# STM32.net
KiCad netlist of a schematic drawn in Altium Designer
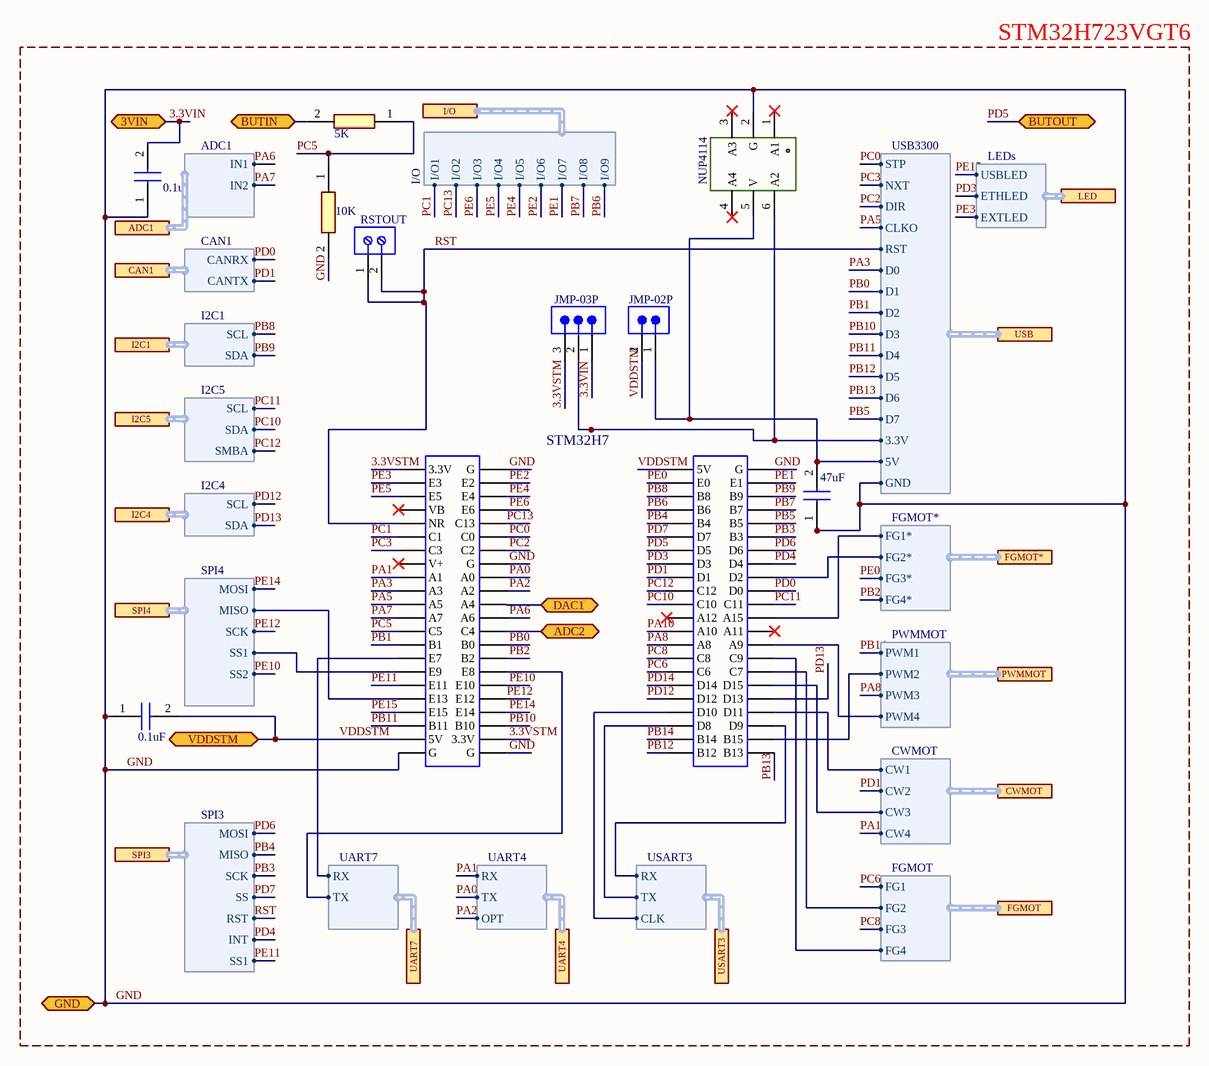
[diagram p0: STM32.SchDoc]

(export (version "E")
  (design (tool "Eeschema 10.0.6"))
  (components
    (comp (ref "BUTIN1")
      (value "5K")
      (footprint "RES0805")
      (description "RES-SMD0805")
      (libsource (lib "Components_Robots") (part "RES0805"))
    )
    (comp (ref "BUTIN2")
      (value "10K")
      (footprint "RES0805")
      (description "RES-SMD0805")
      (libsource (lib "") (part "RES0805_1"))
    )
    (comp (ref "CAP5VUSB")
      (value "47uF")
      (footprint "К10-17Б")
      (description "К10-17Б")
      (libsource (lib "Components_Robots") (part "CAP"))
    )
    (comp (ref "CAPSTM3V")
      (value "0.1uF")
      (footprint "CAP0805")
      (description "CAP-SMD0805")
      (libsource (lib "Components_Robots") (part "CAP0805"))
    )
    (comp (ref "CAPSTM5V")
      (value "0.1uF")
      (footprint "CAP0805")
      (description "CAP-SMD0805")
      (libsource (lib "Components_Robots") (part "CAP0805"))
    )
    (comp (ref "ESDUSB")
      (value "NUP4114")
      (footprint "NUP4114")
      (description "NUP4114HMR6T1G")
      (libsource (lib "Components_Robots") (part "NUP4114"))
    )
    (comp (ref "JMP3VUSB")
      (value "JMP-03P")
      (footprint "JMP-03P")
      (description "PLS-1x3")
      (libsource (lib "Components_Robots") (part "JMP-03P"))
    )
    (comp (ref "JMP5VUSB")
      (value "JMP-02P")
      (footprint "JMP-02P")
      (description "PLS-1x2")
      (libsource (lib "Components_Robots") (part "JMP-02P"))
    )
    (comp (ref "RSTOUT")
      (value "DG127-5.0-02P")
      (footprint "DG127-5.0-02P")
      (description "DG127-5.0-02P-14-00Z")
      (libsource (lib "Components_Robots") (part "DG127-5.0-02P"))
    )
    (comp (ref "STM")
      (value "STM32H7")
      (footprint "STM32H7")
      (description "STM32H723VGT6")
      (libsource (lib "Components_Robots") (part "STM32H7"))
    )
  )
  (nets
    (net (code "18") (name "/3.3V") (class "Default")
      (node (ref "ESDUSB") (pin "6") (pinfunction "A2_6") (pintype "passive"))
      (node (ref "JMP3VUSB") (pin "2") (pinfunction "2_2") (pintype "passive"))
    )
    (net (code "19") (name "/3.3VIN") (class "Default")
      (node (ref "CAPSTM3V") (pin "2") (pinfunction "2_2") (pintype "passive"))
      (node (ref "JMP3VUSB") (pin "1") (pinfunction "1_1") (pintype "passive"))
    )
    (net (code "20") (name "/3.3VSTM") (class "Default")
      (node (ref "JMP3VUSB") (pin "3") (pinfunction "3_3") (pintype "passive"))
      (node (ref "STM") (pin "3.3V") (pinfunction "3.3V_3.3V") (pintype "passive"))
    )
    (net (code "21") (name "/5V") (class "Default")
      (node (ref "CAP5VUSB") (pin "2") (pinfunction "2_2") (pintype "passive"))
      (node (ref "ESDUSB") (pin "5") (pinfunction "V_5") (pintype "passive"))
      (node (ref "JMP5VUSB") (pin "1") (pinfunction "1_1") (pintype "passive"))
    )
    (net (code "22") (name "/ADC2") (class "Default")
      (node (ref "STM") (pin "C4") (pinfunction "C4_C4") (pintype "passive"))
    )
    (net (code "23") (name "/BUTIN") (class "Default")
      (node (ref "BUTIN1") (pin "2") (pinfunction "2_2") (pintype "passive"))
    )
    (net (code "24") (name "/CLK") (class "Default")
      (node (ref "STM") (pin "D10") (pinfunction "D10_D10") (pintype "passive"))
    )
    (net (code "25") (name "/CW1") (class "Default")
      (node (ref "STM") (pin "D11") (pinfunction "D11_D11") (pintype "passive"))
    )
    (net (code "26") (name "/CW3") (class "Default")
      (node (ref "STM") (pin "D15") (pinfunction "D15_D15") (pintype "passive"))
    )
    (net (code "27") (name "/DAC1") (class "Default")
      (node (ref "STM") (pin "A4") (pinfunction "A4_A4") (pintype "passive"))
    )
    (net (code "28") (name "/FG1*") (class "Default")
      (node (ref "STM") (pin "A15") (pinfunction "A15_A15") (pintype "passive"))
    )
    (net (code "29") (name "/FG2") (class "Default")
      (node (ref "STM") (pin "C7") (pinfunction "C7_C7") (pintype "passive"))
    )
    (net (code "30") (name "/FG2*") (class "Default")
      (node (ref "STM") (pin "D2") (pinfunction "D2_D2") (pintype "passive"))
    )
    (net (code "31") (name "/FG4") (class "Default")
      (node (ref "STM") (pin "C9") (pinfunction "C9_C9") (pintype "passive"))
    )
    (net (code "32") (name "/GND") (class "Default")
      (node (ref "BUTIN2") (pin "2") (pinfunction "2_2") (pintype "passive"))
      (node (ref "CAP5VUSB") (pin "1") (pinfunction "1_1") (pintype "passive"))
      (node (ref "CAPSTM3V") (pin "1") (pinfunction "1_1") (pintype "passive"))
      (node (ref "CAPSTM5V") (pin "1") (pinfunction "1_1") (pintype "passive"))
      (node (ref "ESDUSB") (pin "2") (pinfunction "G_2") (pintype "passive"))
      (node (ref "STM") (pin "G") (pinfunction "G_G") (pintype "passive"))
    )
    (net (code "33") (name "/PA0") (class "Default")
      (node (ref "STM") (pin "A0") (pinfunction "A0_A0") (pintype "passive"))
    )
    (net (code "34") (name "/PA1") (class "Default")
      (node (ref "STM") (pin "A1") (pinfunction "A1_A1") (pintype "passive"))
    )
    (net (code "35") (name "/PA2") (class "Default")
      (node (ref "STM") (pin "A2") (pinfunction "A2_A2") (pintype "passive"))
    )
    (net (code "36") (name "/PA3") (class "Default")
      (node (ref "STM") (pin "A3") (pinfunction "A3_A3") (pintype "passive"))
    )
    (net (code "37") (name "/PA5") (class "Default")
      (node (ref "STM") (pin "A5") (pinfunction "A5_A5") (pintype "passive"))
    )
    (net (code "38") (name "/PA6") (class "Default")
      (node (ref "STM") (pin "A6") (pinfunction "A6_A6") (pintype "passive"))
    )
    (net (code "39") (name "/PA7") (class "Default")
      (node (ref "STM") (pin "A7") (pinfunction "A7_A7") (pintype "passive"))
    )
    (net (code "40") (name "/PA8") (class "Default")
      (node (ref "STM") (pin "A8") (pinfunction "A8_A8") (pintype "passive"))
    )
    (net (code "41") (name "/PA10") (class "Default")
      (node (ref "STM") (pin "A10") (pinfunction "A10_A10") (pintype "passive"))
    )
    (net (code "42") (name "/PB0") (class "Default")
      (node (ref "STM") (pin "B0") (pinfunction "B0_B0") (pintype "passive"))
    )
    (net (code "43") (name "/PB1") (class "Default")
      (node (ref "STM") (pin "B1") (pinfunction "B1_B1") (pintype "passive"))
    )
    (net (code "44") (name "/PB2") (class "Default")
      (node (ref "STM") (pin "B2") (pinfunction "B2_B2") (pintype "passive"))
    )
    (net (code "45") (name "/PB3") (class "Default")
      (node (ref "STM") (pin "B3") (pinfunction "B3_B3") (pintype "passive"))
    )
    (net (code "46") (name "/PB4") (class "Default")
      (node (ref "STM") (pin "B4") (pinfunction "B4_B4") (pintype "passive"))
    )
    (net (code "47") (name "/PB5") (class "Default")
      (node (ref "STM") (pin "B5") (pinfunction "B5_B5") (pintype "passive"))
    )
    (net (code "48") (name "/PB6") (class "Default")
      (node (ref "STM") (pin "B6") (pinfunction "B6_B6") (pintype "passive"))
    )
    (net (code "49") (name "/PB7") (class "Default")
      (node (ref "STM") (pin "B7") (pinfunction "B7_B7") (pintype "passive"))
    )
    (net (code "50") (name "/PB8") (class "Default")
      (node (ref "STM") (pin "B8") (pinfunction "B8_B8") (pintype "passive"))
    )
    (net (code "51") (name "/PB9") (class "Default")
      (node (ref "STM") (pin "B9") (pinfunction "B9_B9") (pintype "passive"))
    )
    (net (code "52") (name "/PB10") (class "Default")
      (node (ref "STM") (pin "B10") (pinfunction "B10_B10") (pintype "passive"))
    )
    (net (code "53") (name "/PB11") (class "Default")
      (node (ref "STM") (pin "B11") (pinfunction "B11_B11") (pintype "passive"))
    )
    (net (code "54") (name "/PB12") (class "Default")
      (node (ref "STM") (pin "B12") (pinfunction "B12_B12") (pintype "passive"))
    )
    (net (code "55") (name "/PB13") (class "Default")
      (node (ref "STM") (pin "B13") (pinfunction "B13_B13") (pintype "passive"))
    )
    (net (code "56") (name "/PB14") (class "Default")
      (node (ref "STM") (pin "B14") (pinfunction "B14_B14") (pintype "passive"))
    )
    (net (code "57") (name "/PC0") (class "Default")
      (node (ref "STM") (pin "C0") (pinfunction "C0_C0") (pintype "passive"))
    )
    (net (code "58") (name "/PC1") (class "Default")
      (node (ref "STM") (pin "C1") (pinfunction "C1_C1") (pintype "passive"))
    )
    (net (code "59") (name "/PC2") (class "Default")
      (node (ref "STM") (pin "C2") (pinfunction "C2_C2") (pintype "passive"))
    )
    (net (code "60") (name "/PC3") (class "Default")
      (node (ref "STM") (pin "C3") (pinfunction "C3_C3") (pintype "passive"))
    )
    (net (code "61") (name "/PC5") (class "Default")
      (node (ref "BUTIN1") (pin "1") (pinfunction "1_1") (pintype "passive"))
      (node (ref "BUTIN2") (pin "1") (pinfunction "1_1") (pintype "passive"))
      (node (ref "STM") (pin "C5") (pinfunction "C5_C5") (pintype "passive"))
    )
    (net (code "62") (name "/PC6") (class "Default")
      (node (ref "STM") (pin "C6") (pinfunction "C6_C6") (pintype "passive"))
    )
    (net (code "63") (name "/PC8") (class "Default")
      (node (ref "STM") (pin "C8") (pinfunction "C8_C8") (pintype "passive"))
    )
    (net (code "64") (name "/PC10") (class "Default")
      (node (ref "STM") (pin "C10") (pinfunction "C10_C10") (pintype "passive"))
    )
    (net (code "65") (name "/PC11") (class "Default")
      (node (ref "STM") (pin "C11") (pinfunction "C11_C11") (pintype "passive"))
    )
    (net (code "66") (name "/PC12") (class "Default")
      (node (ref "STM") (pin "C12") (pinfunction "C12_C12") (pintype "passive"))
    )
    (net (code "67") (name "/PC13") (class "Default")
      (node (ref "STM") (pin "C13") (pinfunction "C13_C13") (pintype "passive"))
    )
    (net (code "68") (name "/PD0") (class "Default")
      (node (ref "STM") (pin "D0") (pinfunction "D0_D0") (pintype "passive"))
    )
    (net (code "69") (name "/PD1") (class "Default")
      (node (ref "STM") (pin "D1") (pinfunction "D1_D1") (pintype "passive"))
    )
    (net (code "70") (name "/PD3") (class "Default")
      (node (ref "STM") (pin "D3") (pinfunction "D3_D3") (pintype "passive"))
    )
    (net (code "71") (name "/PD4") (class "Default")
      (node (ref "STM") (pin "D4") (pinfunction "D4_D4") (pintype "passive"))
    )
    (net (code "72") (name "/PD5") (class "Default")
      (node (ref "STM") (pin "D5") (pinfunction "D5_D5") (pintype "passive"))
    )
    (net (code "73") (name "/PD6") (class "Default")
      (node (ref "STM") (pin "D6") (pinfunction "D6_D6") (pintype "passive"))
    )
    (net (code "74") (name "/PD7") (class "Default")
      (node (ref "STM") (pin "D7") (pinfunction "D7_D7") (pintype "passive"))
    )
    (net (code "75") (name "/PD12") (class "Default")
      (node (ref "STM") (pin "D12") (pinfunction "D12_D12") (pintype "passive"))
    )
    (net (code "76") (name "/PD13") (class "Default")
      (node (ref "STM") (pin "D13") (pinfunction "D13_D13") (pintype "passive"))
    )
    (net (code "77") (name "/PD14") (class "Default")
      (node (ref "STM") (pin "D14") (pinfunction "D14_D14") (pintype "passive"))
    )
    (net (code "78") (name "/PE0") (class "Default")
      (node (ref "STM") (pin "E0") (pinfunction "E0_E0") (pintype "passive"))
    )
    (net (code "79") (name "/PE1") (class "Default")
      (node (ref "STM") (pin "E1") (pinfunction "E1_E1") (pintype "passive"))
    )
    (net (code "80") (name "/PE2") (class "Default")
      (node (ref "STM") (pin "E2") (pinfunction "E2_E2") (pintype "passive"))
    )
    (net (code "81") (name "/PE3") (class "Default")
      (node (ref "STM") (pin "E3") (pinfunction "E3_E3") (pintype "passive"))
    )
    (net (code "82") (name "/PE4") (class "Default")
      (node (ref "STM") (pin "E4") (pinfunction "E4_E4") (pintype "passive"))
    )
    (net (code "83") (name "/PE5") (class "Default")
      (node (ref "STM") (pin "E5") (pinfunction "E5_E5") (pintype "passive"))
    )
    (net (code "84") (name "/PE6") (class "Default")
      (node (ref "STM") (pin "E6") (pinfunction "E6_E6") (pintype "passive"))
    )
    (net (code "85") (name "/PE10") (class "Default")
      (node (ref "STM") (pin "E10") (pinfunction "E10_E10") (pintype "passive"))
    )
    (net (code "86") (name "/PE11") (class "Default")
      (node (ref "STM") (pin "E11") (pinfunction "E11_E11") (pintype "passive"))
    )
    (net (code "87") (name "/PE12") (class "Default")
      (node (ref "STM") (pin "E12") (pinfunction "E12_E12") (pintype "passive"))
    )
    (net (code "88") (name "/PE14") (class "Default")
      (node (ref "STM") (pin "E14") (pinfunction "E14_E14") (pintype "passive"))
    )
    (net (code "89") (name "/PE15") (class "Default")
      (node (ref "STM") (pin "E15") (pinfunction "E15_E15") (pintype "passive"))
    )
    (net (code "90") (name "/PWM2") (class "Default")
      (node (ref "STM") (pin "B15") (pinfunction "B15_B15") (pintype "passive"))
    )
    (net (code "91") (name "/PWM4") (class "Default")
      (node (ref "STM") (pin "A9") (pinfunction "A9_A9") (pintype "passive"))
    )
    (net (code "92") (name "/RST") (class "Default")
      (node (ref "RSTOUT") (pin "1") (pinfunction "1_1") (pintype "passive"))
      (node (ref "RSTOUT") (pin "2") (pinfunction "2_2") (pintype "passive"))
      (node (ref "STM") (pin "NR") (pinfunction "NR_NR") (pintype "passive"))
    )
    (net (code "93") (name "/VDDSTM") (class "Default")
      (node (ref "CAPSTM5V") (pin "2") (pinfunction "2_2") (pintype "passive"))
      (node (ref "JMP5VUSB") (pin "2") (pinfunction "2_2") (pintype "passive"))
      (node (ref "STM") (pin "5V") (pinfunction "5V_5V") (pintype "passive"))
    )
    (net (code "111") (name "unconnected-(ESDUSB-A1-Pad1)") (class "Default")
      (node (ref "ESDUSB") (pin "1") (pinfunction "A1_1") (pintype "passive+no_connect"))
    )
    (net (code "112") (name "unconnected-(ESDUSB-A3-Pad3)") (class "Default")
      (node (ref "ESDUSB") (pin "3") (pinfunction "A3_3") (pintype "passive+no_connect"))
    )
    (net (code "113") (name "unconnected-(ESDUSB-A4-Pad4)") (class "Default")
      (node (ref "ESDUSB") (pin "4") (pinfunction "A4_4") (pintype "passive+no_connect"))
    )
    (net (code "114") (name "unconnected-(STM-PadA11)") (class "Default")
      (node (ref "STM") (pin "A11") (pinfunction "A11_A11") (pintype "passive+no_connect"))
    )
    (net (code "115") (name "unconnected-(STM-PadA12)") (class "Default")
      (node (ref "STM") (pin "A12") (pinfunction "A12_A12") (pintype "passive+no_connect"))
    )
    (net (code "116") (name "unconnected-(STM-PadD8)") (class "Default")
      (node (ref "STM") (pin "D8") (pinfunction "D8_D8") (pintype "passive"))
    )
    (net (code "117") (name "unconnected-(STM-PadD9)") (class "Default")
      (node (ref "STM") (pin "D9") (pinfunction "D9_D9") (pintype "passive"))
    )
    (net (code "118") (name "unconnected-(STM-PadE7)") (class "Default")
      (node (ref "STM") (pin "E7") (pinfunction "E7_E7") (pintype "passive"))
    )
    (net (code "119") (name "unconnected-(STM-PadE8)") (class "Default")
      (node (ref "STM") (pin "E8") (pinfunction "E8_E8") (pintype "passive"))
    )
    (net (code "120") (name "unconnected-(STM-PadE9)") (class "Default")
      (node (ref "STM") (pin "E9") (pinfunction "E9_E9") (pintype "passive"))
    )
    (net (code "121") (name "unconnected-(STM-PadE13)") (class "Default")
      (node (ref "STM") (pin "E13") (pinfunction "E13_E13") (pintype "passive"))
    )
    (net (code "122") (name "unconnected-(STM-PadV+)") (class "Default")
      (node (ref "STM") (pin "V+") (pinfunction "V+_V+") (pintype "passive+no_connect"))
    )
    (net (code "123") (name "unconnected-(STM-PadVB)") (class "Default")
      (node (ref "STM") (pin "VB") (pinfunction "VB_VB") (pintype "passive+no_connect"))
    )
  )
)
